# L010F4P6.net
KiCad netlist of a schematic drawn in EAGLE
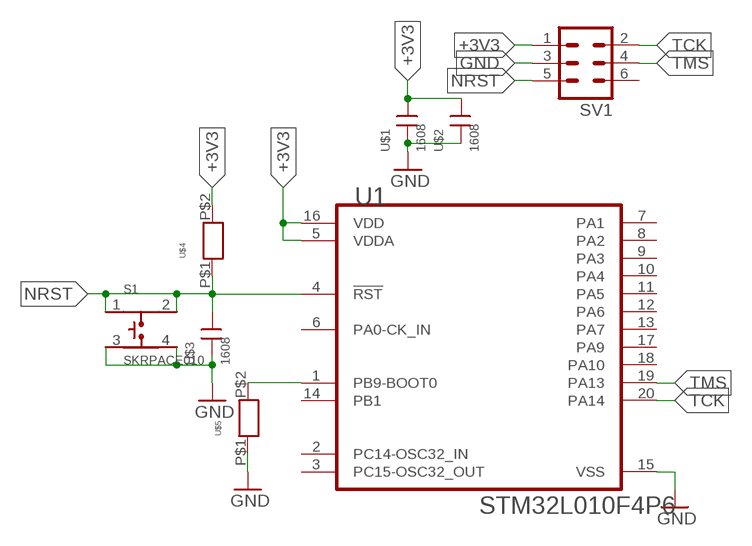
[diagram p0: schematic, sheet 1]

(export (version "E")
  (design (tool "Eeschema 10.0.6"))
  (components
    (comp (ref "S1")
      (value "SKRPACE010")
      (footprint "eagle-import:SW_SKRPACE010")
      (fields (field (name "MF") "ALPS"))
      (libsource (lib "eagle-import") (part "SKRPACE010"))
    )
    (comp (ref "SV1")
      (value "ML6")
      (footprint "eagle-import:ML6")
      (libsource (lib "eagle-import") (part "ML6"))
    )
    (comp (ref "U$1")
      (value "1608")
      (footprint "eagle-import:CON")
      (libsource (lib "eagle-import") (part "1608"))
    )
    (comp (ref "U$2")
      (value "1608")
      (footprint "eagle-import:CON")
      (libsource (lib "eagle-import") (part "1608"))
    )
    (comp (ref "U$3")
      (value "1608")
      (footprint "eagle-import:CON")
      (libsource (lib "eagle-import") (part "1608"))
    )
    (comp (ref "U$4") (value "R") (footprint "eagle-import:1608") (libsource (lib "eagle-import") (part "R")))
    (comp (ref "U$5") (value "R") (footprint "eagle-import:1608") (libsource (lib "eagle-import") (part "R")))
    (comp (ref "U1")
      (value "STMICROELECTRONICS_STM32L010F4P6STMICROELECTRONICS_STM32L010F4P6_0_0")
      (footprint "eagle-import:STMICROELECTRONICS_STM32L010F4P6_0")
      (fields
        (field (name "DIGIKEY_PART_NUMBER") "497-19364-ND")
        (field (name "MF") "STMicroelectronics")
        (field (name "MOUSER_PART_NUMBER") "511-STM32L010F4P6")
      )
      (libsource (lib "eagle-import") (part "STMICROELECTRONICS_STM32L010F4P6STMICROELECTRONICS_STM32L010F4P6_0_0"))
    )
  )
  (nets
    (net (code "1") (name "+3V3") (class "Default")
      (node (ref "SV1") (pin "1") (pinfunction "1_1") (pintype "passive"))
      (node (ref "U$1") (pin "P$1") (pinfunction "1_P$1") (pintype "bidirectional"))
      (node (ref "U$2") (pin "P$1") (pinfunction "1_P$1") (pintype "bidirectional"))
      (node (ref "U$4") (pin "P$2") (pinfunction "P$2_P$2") (pintype "bidirectional"))
      (node (ref "U1") (pin "16") (pinfunction "VDD_16") (pintype "power_in"))
      (node (ref "U1") (pin "5") (pinfunction "VDDA_5") (pintype "power_in"))
    )
    (net (code "2") (name "GND") (class "Default")
      (node (ref "S1") (pin "3") (pinfunction "3_3") (pintype "bidirectional"))
      (node (ref "S1") (pin "4") (pinfunction "4_4") (pintype "bidirectional"))
      (node (ref "SV1") (pin "3") (pinfunction "3_3") (pintype "passive"))
      (node (ref "U$1") (pin "P$2") (pinfunction "2_P$2") (pintype "bidirectional"))
      (node (ref "U$2") (pin "P$2") (pinfunction "2_P$2") (pintype "bidirectional"))
      (node (ref "U$3") (pin "P$2") (pinfunction "2_P$2") (pintype "bidirectional"))
      (node (ref "U$5") (pin "P$1") (pinfunction "P$1_P$1") (pintype "bidirectional"))
      (node (ref "U1") (pin "15") (pinfunction "VSS_15") (pintype "power_in"))
    )
    (net (code "3") (name "NRST") (class "Default")
      (node (ref "S1") (pin "1") (pinfunction "1_1") (pintype "bidirectional"))
      (node (ref "S1") (pin "2") (pinfunction "2_2") (pintype "bidirectional"))
      (node (ref "SV1") (pin "5") (pinfunction "5_5") (pintype "passive"))
      (node (ref "U$3") (pin "P$1") (pinfunction "1_P$1") (pintype "bidirectional"))
      (node (ref "U$4") (pin "P$1") (pinfunction "P$1_P$1") (pintype "bidirectional"))
      (node (ref "U1") (pin "4") (pinfunction "~{RST}_4") (pintype "input"))
    )
    (net (code "4") (name "Net-(U1-PB9-BOOT0)") (class "Default")
      (node (ref "U$5") (pin "P$2") (pinfunction "P$2_P$2") (pintype "bidirectional"))
      (node (ref "U1") (pin "1") (pinfunction "PB9-BOOT0_1") (pintype "input"))
    )
    (net (code "5") (name "TCK") (class "Default")
      (node (ref "SV1") (pin "2") (pinfunction "2_2") (pintype "passive"))
      (node (ref "U1") (pin "20") (pinfunction "PA14_20") (pintype "bidirectional"))
    )
    (net (code "6") (name "TMS") (class "Default")
      (node (ref "SV1") (pin "4") (pinfunction "4_4") (pintype "passive"))
      (node (ref "U1") (pin "19") (pinfunction "PA13_19") (pintype "bidirectional"))
    )
    (net (code "7") (name "unconnected-(SV1-Pad6)") (class "Default")
      (node (ref "SV1") (pin "6") (pinfunction "6_6") (pintype "passive"))
    )
    (net (code "8") (name "unconnected-(U1-PA0-CK_IN-Pad6)") (class "Default")
      (node (ref "U1") (pin "6") (pinfunction "PA0-CK_IN_6") (pintype "bidirectional"))
    )
    (net (code "9") (name "unconnected-(U1-PA1-Pad7)") (class "Default")
      (node (ref "U1") (pin "7") (pinfunction "PA1_7") (pintype "bidirectional"))
    )
    (net (code "10") (name "unconnected-(U1-PA2-Pad8)") (class "Default")
      (node (ref "U1") (pin "8") (pinfunction "PA2_8") (pintype "bidirectional"))
    )
    (net (code "11") (name "unconnected-(U1-PA3-Pad9)") (class "Default")
      (node (ref "U1") (pin "9") (pinfunction "PA3_9") (pintype "bidirectional"))
    )
    (net (code "12") (name "unconnected-(U1-PA4-Pad10)") (class "Default")
      (node (ref "U1") (pin "10") (pinfunction "PA4_10") (pintype "bidirectional"))
    )
    (net (code "13") (name "unconnected-(U1-PA5-Pad11)") (class "Default")
      (node (ref "U1") (pin "11") (pinfunction "PA5_11") (pintype "bidirectional"))
    )
    (net (code "14") (name "unconnected-(U1-PA6-Pad12)") (class "Default")
      (node (ref "U1") (pin "12") (pinfunction "PA6_12") (pintype "bidirectional"))
    )
    (net (code "15") (name "unconnected-(U1-PA7-Pad13)") (class "Default")
      (node (ref "U1") (pin "13") (pinfunction "PA7_13") (pintype "bidirectional"))
    )
    (net (code "16") (name "unconnected-(U1-PA9-Pad17)") (class "Default")
      (node (ref "U1") (pin "17") (pinfunction "PA9_17") (pintype "bidirectional"))
    )
    (net (code "17") (name "unconnected-(U1-PA10-Pad18)") (class "Default")
      (node (ref "U1") (pin "18") (pinfunction "PA10_18") (pintype "bidirectional"))
    )
    (net (code "18") (name "unconnected-(U1-PB1-Pad14)") (class "Default")
      (node (ref "U1") (pin "14") (pinfunction "PB1_14") (pintype "bidirectional"))
    )
    (net (code "19") (name "unconnected-(U1-PC14-OSC32_IN-Pad2)") (class "Default")
      (node (ref "U1") (pin "2") (pinfunction "PC14-OSC32_IN_2") (pintype "bidirectional"))
    )
    (net (code "20") (name "unconnected-(U1-PC15-OSC32_OUT-Pad3)") (class "Default")
      (node (ref "U1") (pin "3") (pinfunction "PC15-OSC32_OUT_3") (pintype "bidirectional"))
    )
  )
)
